# nes_controller_v1_0.net
KiCad netlist of a schematic drawn in EAGLE
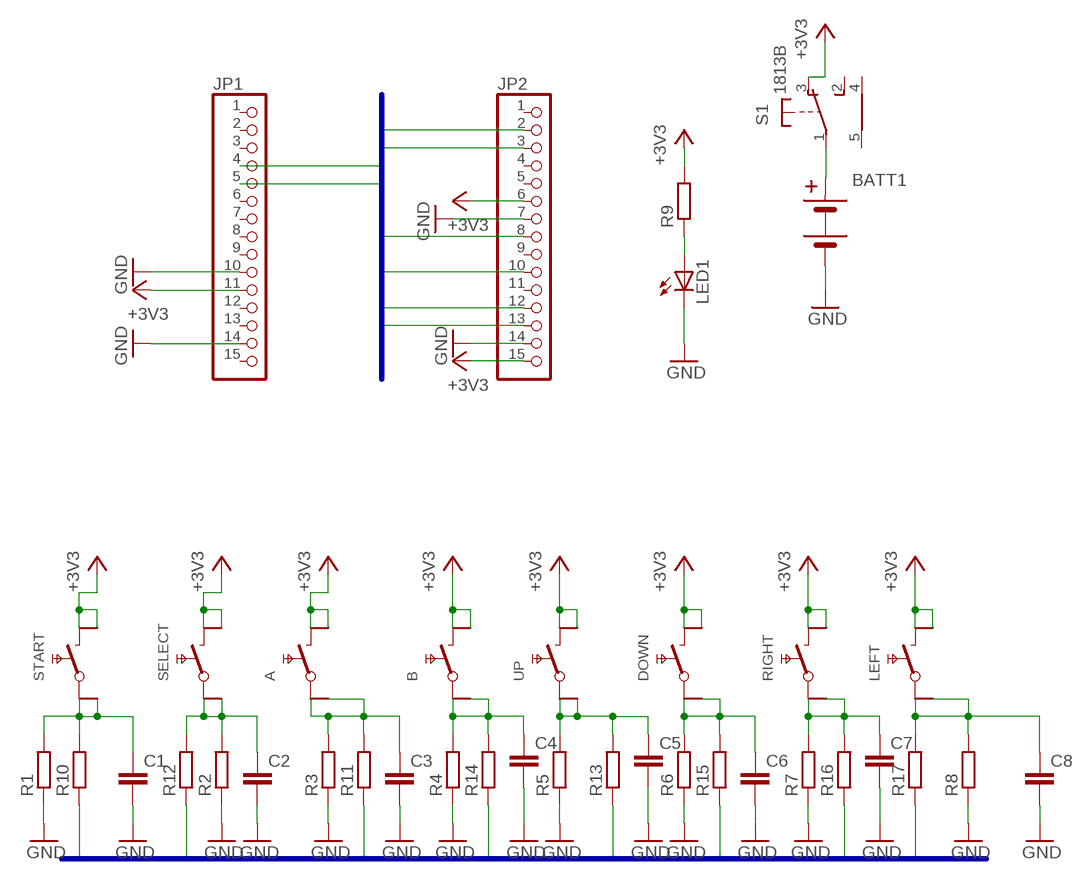
[diagram p0: schematic, sheet 1]

(export (version "E")
  (design (tool "Eeschema 10.0.6"))
  (components
    (comp (ref "A")
      (value "SMDTAST")
      (footprint "eagle-import:SMDTAST")
      (libsource (lib "eagle-import") (part "SMDTAST"))
    )
    (comp (ref "B")
      (value "SMDTAST")
      (footprint "eagle-import:SMDTAST")
      (libsource (lib "eagle-import") (part "SMDTAST"))
    )
    (comp (ref "BATT1")
      (value "BATTERIEHALTER_2X_AAA")
      (footprint "eagle-import:BATTERIEHALTER")
      (libsource (lib "eagle-import") (part "BATTERIEHALTER_2X_AAA"))
    )
    (comp (ref "C1")
      (value "C-EUC0805K")
      (footprint "eagle-import:C0805K")
      (libsource (lib "eagle-import") (part "C-EUC0805K"))
    )
    (comp (ref "C2")
      (value "C-EUC0805K")
      (footprint "eagle-import:C0805K")
      (libsource (lib "eagle-import") (part "C-EUC0805K"))
    )
    (comp (ref "C3")
      (value "C-EUC0805K")
      (footprint "eagle-import:C0805K")
      (libsource (lib "eagle-import") (part "C-EUC0805K"))
    )
    (comp (ref "C4")
      (value "C-EUC0805K")
      (footprint "eagle-import:C0805K")
      (libsource (lib "eagle-import") (part "C-EUC0805K"))
    )
    (comp (ref "C5")
      (value "C-EUC0805K")
      (footprint "eagle-import:C0805K")
      (libsource (lib "eagle-import") (part "C-EUC0805K"))
    )
    (comp (ref "C6")
      (value "C-EUC0805K")
      (footprint "eagle-import:C0805K")
      (libsource (lib "eagle-import") (part "C-EUC0805K"))
    )
    (comp (ref "C7")
      (value "C-EUC0805K")
      (footprint "eagle-import:C0805K")
      (libsource (lib "eagle-import") (part "C-EUC0805K"))
    )
    (comp (ref "C8")
      (value "C-EUC0805K")
      (footprint "eagle-import:C0805K")
      (libsource (lib "eagle-import") (part "C-EUC0805K"))
    )
    (comp (ref "DOWN")
      (value "SMDTAST")
      (footprint "eagle-import:SMDTAST")
      (libsource (lib "eagle-import") (part "SMDTAST"))
    )
    (comp (ref "JP1")
      (value "PINHD-1X15")
      (footprint "eagle-import:1X15")
      (libsource (lib "eagle-import") (part "PINHD-1X15"))
    )
    (comp (ref "JP2")
      (value "PINHD-1X15")
      (footprint "eagle-import:1X15")
      (libsource (lib "eagle-import") (part "PINHD-1X15"))
    )
    (comp (ref "LED1")
      (value "LED3MM")
      (footprint "eagle-import:LED3MM")
      (libsource (lib "eagle-import") (part "LED3MM"))
    )
    (comp (ref "LEFT")
      (value "SMDTAST")
      (footprint "eagle-import:SMDTAST")
      (libsource (lib "eagle-import") (part "SMDTAST"))
    )
    (comp (ref "R1")
      (value "R-EU_R1206")
      (footprint "eagle-import:R1206")
      (libsource (lib "eagle-import") (part "R-EU_R1206"))
    )
    (comp (ref "R2")
      (value "R-EU_R1206")
      (footprint "eagle-import:R1206")
      (libsource (lib "eagle-import") (part "R-EU_R1206"))
    )
    (comp (ref "R3")
      (value "R-EU_R1206")
      (footprint "eagle-import:R1206")
      (libsource (lib "eagle-import") (part "R-EU_R1206"))
    )
    (comp (ref "R4")
      (value "R-EU_R1206")
      (footprint "eagle-import:R1206")
      (libsource (lib "eagle-import") (part "R-EU_R1206"))
    )
    (comp (ref "R5")
      (value "R-EU_R1206")
      (footprint "eagle-import:R1206")
      (libsource (lib "eagle-import") (part "R-EU_R1206"))
    )
    (comp (ref "R6")
      (value "R-EU_R1206")
      (footprint "eagle-import:R1206")
      (libsource (lib "eagle-import") (part "R-EU_R1206"))
    )
    (comp (ref "R7")
      (value "R-EU_R1206")
      (footprint "eagle-import:R1206")
      (libsource (lib "eagle-import") (part "R-EU_R1206"))
    )
    (comp (ref "R8")
      (value "R-EU_R1206")
      (footprint "eagle-import:R1206")
      (libsource (lib "eagle-import") (part "R-EU_R1206"))
    )
    (comp (ref "R9")
      (value "R-EU_R1206")
      (footprint "eagle-import:R1206")
      (libsource (lib "eagle-import") (part "R-EU_R1206"))
    )
    (comp (ref "R10")
      (value "R-EU_R1206")
      (footprint "eagle-import:R1206")
      (libsource (lib "eagle-import") (part "R-EU_R1206"))
    )
    (comp (ref "R11")
      (value "R-EU_R1206")
      (footprint "eagle-import:R1206")
      (libsource (lib "eagle-import") (part "R-EU_R1206"))
    )
    (comp (ref "R12")
      (value "R-EU_R1206")
      (footprint "eagle-import:R1206")
      (libsource (lib "eagle-import") (part "R-EU_R1206"))
    )
    (comp (ref "R13")
      (value "R-EU_R1206")
      (footprint "eagle-import:R1206")
      (libsource (lib "eagle-import") (part "R-EU_R1206"))
    )
    (comp (ref "R14")
      (value "R-EU_R1206")
      (footprint "eagle-import:R1206")
      (libsource (lib "eagle-import") (part "R-EU_R1206"))
    )
    (comp (ref "R15")
      (value "R-EU_R1206")
      (footprint "eagle-import:R1206")
      (libsource (lib "eagle-import") (part "R-EU_R1206"))
    )
    (comp (ref "R16")
      (value "R-EU_R1206")
      (footprint "eagle-import:R1206")
      (libsource (lib "eagle-import") (part "R-EU_R1206"))
    )
    (comp (ref "R17")
      (value "R-EU_R1206")
      (footprint "eagle-import:R1206")
      (libsource (lib "eagle-import") (part "R-EU_R1206"))
    )
    (comp (ref "RIGHT")
      (value "SMDTAST")
      (footprint "eagle-import:SMDTAST")
      (libsource (lib "eagle-import") (part "SMDTAST"))
    )
    (comp (ref "S1")
      (value "1813B")
      (footprint "eagle-import:1813B")
      (libsource (lib "eagle-import") (part "1813B"))
    )
    (comp (ref "SELECT")
      (value "SMDTAST")
      (footprint "eagle-import:SMDTAST")
      (libsource (lib "eagle-import") (part "SMDTAST"))
    )
    (comp (ref "START")
      (value "SMDTAST")
      (footprint "eagle-import:SMDTAST")
      (libsource (lib "eagle-import") (part "SMDTAST"))
    )
    (comp (ref "UP")
      (value "SMDTAST")
      (footprint "eagle-import:SMDTAST")
      (libsource (lib "eagle-import") (part "SMDTAST"))
    )
  )
  (nets
    (net (code "1") (name "+3V3") (class "Default")
      (node (ref "A") (pin "2") (pinfunction "2_2") (pintype "bidirectional"))
      (node (ref "A") (pin "22") (pinfunction "22_22") (pintype "bidirectional"))
      (node (ref "B") (pin "2") (pinfunction "2_2") (pintype "bidirectional"))
      (node (ref "B") (pin "22") (pinfunction "22_22") (pintype "bidirectional"))
      (node (ref "DOWN") (pin "2") (pinfunction "2_2") (pintype "bidirectional"))
      (node (ref "DOWN") (pin "22") (pinfunction "22_22") (pintype "bidirectional"))
      (node (ref "JP1") (pin "11") (pinfunction "11_11") (pintype "passive"))
      (node (ref "JP2") (pin "15") (pinfunction "15_15") (pintype "passive"))
      (node (ref "JP2") (pin "6") (pinfunction "6_6") (pintype "passive"))
      (node (ref "LEFT") (pin "2") (pinfunction "2_2") (pintype "bidirectional"))
      (node (ref "LEFT") (pin "22") (pinfunction "22_22") (pintype "bidirectional"))
      (node (ref "R9") (pin "2") (pinfunction "2_2") (pintype "passive"))
      (node (ref "RIGHT") (pin "2") (pinfunction "2_2") (pintype "bidirectional"))
      (node (ref "RIGHT") (pin "22") (pinfunction "22_22") (pintype "bidirectional"))
      (node (ref "S1") (pin "3") (pinfunction "O_3") (pintype "passive"))
      (node (ref "SELECT") (pin "2") (pinfunction "2_2") (pintype "bidirectional"))
      (node (ref "SELECT") (pin "22") (pinfunction "22_22") (pintype "bidirectional"))
      (node (ref "START") (pin "2") (pinfunction "2_2") (pintype "bidirectional"))
      (node (ref "START") (pin "22") (pinfunction "22_22") (pintype "bidirectional"))
      (node (ref "UP") (pin "2") (pinfunction "2_2") (pintype "bidirectional"))
      (node (ref "UP") (pin "22") (pinfunction "22_22") (pintype "bidirectional"))
    )
    (net (code "2") (name "/A") (class "Default")
      (node (ref "JP1") (pin "5") (pinfunction "5_5") (pintype "passive"))
      (node (ref "R11") (pin "1") (pinfunction "1_1") (pintype "passive"))
    )
    (net (code "3") (name "/B") (class "Default")
      (node (ref "JP1") (pin "4") (pinfunction "4_4") (pintype "passive"))
      (node (ref "R14") (pin "1") (pinfunction "1_1") (pintype "passive"))
    )
    (net (code "4") (name "/DOWN") (class "Default")
      (node (ref "JP2") (pin "10") (pinfunction "10_10") (pintype "passive"))
      (node (ref "R15") (pin "1") (pinfunction "1_1") (pintype "passive"))
    )
    (net (code "5") (name "/LEFT") (class "Default")
      (node (ref "JP2") (pin "3") (pinfunction "3_3") (pintype "passive"))
      (node (ref "R17") (pin "1") (pinfunction "1_1") (pintype "passive"))
    )
    (net (code "6") (name "/RIGHT") (class "Default")
      (node (ref "JP2") (pin "8") (pinfunction "8_8") (pintype "passive"))
      (node (ref "R16") (pin "1") (pinfunction "1_1") (pintype "passive"))
    )
    (net (code "7") (name "/SELECT") (class "Default")
      (node (ref "JP2") (pin "12") (pinfunction "12_12") (pintype "passive"))
      (node (ref "R12") (pin "1") (pinfunction "1_1") (pintype "passive"))
    )
    (net (code "8") (name "/START") (class "Default")
      (node (ref "JP2") (pin "13") (pinfunction "13_13") (pintype "passive"))
      (node (ref "R10") (pin "1") (pinfunction "1_1") (pintype "passive"))
    )
    (net (code "9") (name "/UP") (class "Default")
      (node (ref "JP2") (pin "2") (pinfunction "2_2") (pintype "passive"))
      (node (ref "R13") (pin "1") (pinfunction "1_1") (pintype "passive"))
    )
    (net (code "11") (name "GND") (class "Default")
      (node (ref "BATT1") (pin "P-") (pinfunction "P-_P-") (pintype "bidirectional"))
      (node (ref "C1") (pin "2") (pinfunction "2_2") (pintype "passive"))
      (node (ref "C2") (pin "2") (pinfunction "2_2") (pintype "passive"))
      (node (ref "C3") (pin "2") (pinfunction "2_2") (pintype "passive"))
      (node (ref "C4") (pin "2") (pinfunction "2_2") (pintype "passive"))
      (node (ref "C5") (pin "2") (pinfunction "2_2") (pintype "passive"))
      (node (ref "C6") (pin "2") (pinfunction "2_2") (pintype "passive"))
      (node (ref "C7") (pin "2") (pinfunction "2_2") (pintype "passive"))
      (node (ref "C8") (pin "2") (pinfunction "2_2") (pintype "passive"))
      (node (ref "JP1") (pin "10") (pinfunction "10_10") (pintype "passive"))
      (node (ref "JP1") (pin "14") (pinfunction "14_14") (pintype "passive"))
      (node (ref "JP2") (pin "14") (pinfunction "14_14") (pintype "passive"))
      (node (ref "JP2") (pin "7") (pinfunction "7_7") (pintype "passive"))
      (node (ref "LED1") (pin "K") (pinfunction "C_K") (pintype "passive"))
      (node (ref "R1") (pin "1") (pinfunction "1_1") (pintype "passive"))
      (node (ref "R2") (pin "1") (pinfunction "1_1") (pintype "passive"))
      (node (ref "R3") (pin "1") (pinfunction "1_1") (pintype "passive"))
      (node (ref "R4") (pin "1") (pinfunction "1_1") (pintype "passive"))
      (node (ref "R5") (pin "1") (pinfunction "1_1") (pintype "passive"))
      (node (ref "R6") (pin "1") (pinfunction "1_1") (pintype "passive"))
      (node (ref "R7") (pin "1") (pinfunction "1_1") (pintype "passive"))
      (node (ref "R8") (pin "1") (pinfunction "1_1") (pintype "passive"))
    )
    (net (code "12") (name "Net-(A-Pad1)") (class "Default")
      (node (ref "A") (pin "1") (pinfunction "1_1") (pintype "bidirectional"))
      (node (ref "A") (pin "11") (pinfunction "11_11") (pintype "bidirectional"))
      (node (ref "C3") (pin "1") (pinfunction "1_1") (pintype "passive"))
      (node (ref "R11") (pin "2") (pinfunction "2_2") (pintype "passive"))
      (node (ref "R3") (pin "2") (pinfunction "2_2") (pintype "passive"))
    )
    (net (code "13") (name "Net-(B-Pad1)") (class "Default")
      (node (ref "B") (pin "1") (pinfunction "1_1") (pintype "bidirectional"))
      (node (ref "B") (pin "11") (pinfunction "11_11") (pintype "bidirectional"))
      (node (ref "C4") (pin "1") (pinfunction "1_1") (pintype "passive"))
      (node (ref "R14") (pin "2") (pinfunction "2_2") (pintype "passive"))
      (node (ref "R4") (pin "2") (pinfunction "2_2") (pintype "passive"))
    )
    (net (code "14") (name "Net-(C1-Pad1)") (class "Default")
      (node (ref "C1") (pin "1") (pinfunction "1_1") (pintype "passive"))
      (node (ref "R1") (pin "2") (pinfunction "2_2") (pintype "passive"))
      (node (ref "R10") (pin "2") (pinfunction "2_2") (pintype "passive"))
      (node (ref "START") (pin "1") (pinfunction "1_1") (pintype "bidirectional"))
      (node (ref "START") (pin "11") (pinfunction "11_11") (pintype "bidirectional"))
    )
    (net (code "15") (name "Net-(C2-Pad1)") (class "Default")
      (node (ref "C2") (pin "1") (pinfunction "1_1") (pintype "passive"))
      (node (ref "R12") (pin "2") (pinfunction "2_2") (pintype "passive"))
      (node (ref "R2") (pin "2") (pinfunction "2_2") (pintype "passive"))
      (node (ref "SELECT") (pin "1") (pinfunction "1_1") (pintype "bidirectional"))
      (node (ref "SELECT") (pin "11") (pinfunction "11_11") (pintype "bidirectional"))
    )
    (net (code "16") (name "Net-(C5-Pad1)") (class "Default")
      (node (ref "C5") (pin "1") (pinfunction "1_1") (pintype "passive"))
      (node (ref "R13") (pin "2") (pinfunction "2_2") (pintype "passive"))
      (node (ref "R5") (pin "2") (pinfunction "2_2") (pintype "passive"))
      (node (ref "UP") (pin "1") (pinfunction "1_1") (pintype "bidirectional"))
      (node (ref "UP") (pin "11") (pinfunction "11_11") (pintype "bidirectional"))
    )
    (net (code "17") (name "Net-(C6-Pad1)") (class "Default")
      (node (ref "C6") (pin "1") (pinfunction "1_1") (pintype "passive"))
      (node (ref "DOWN") (pin "1") (pinfunction "1_1") (pintype "bidirectional"))
      (node (ref "DOWN") (pin "11") (pinfunction "11_11") (pintype "bidirectional"))
      (node (ref "R15") (pin "2") (pinfunction "2_2") (pintype "passive"))
      (node (ref "R6") (pin "2") (pinfunction "2_2") (pintype "passive"))
    )
    (net (code "18") (name "Net-(C7-Pad1)") (class "Default")
      (node (ref "C7") (pin "1") (pinfunction "1_1") (pintype "passive"))
      (node (ref "R16") (pin "2") (pinfunction "2_2") (pintype "passive"))
      (node (ref "R7") (pin "2") (pinfunction "2_2") (pintype "passive"))
      (node (ref "RIGHT") (pin "1") (pinfunction "1_1") (pintype "bidirectional"))
      (node (ref "RIGHT") (pin "11") (pinfunction "11_11") (pintype "bidirectional"))
    )
    (net (code "19") (name "Net-(C8-Pad1)") (class "Default")
      (node (ref "C8") (pin "1") (pinfunction "1_1") (pintype "passive"))
      (node (ref "LEFT") (pin "1") (pinfunction "1_1") (pintype "bidirectional"))
      (node (ref "LEFT") (pin "11") (pinfunction "11_11") (pintype "bidirectional"))
      (node (ref "R17") (pin "2") (pinfunction "2_2") (pintype "passive"))
      (node (ref "R8") (pin "2") (pinfunction "2_2") (pintype "passive"))
    )
    (net (code "20") (name "Net-(LED1-PadA)") (class "Default")
      (node (ref "LED1") (pin "A") (pinfunction "A_A") (pintype "passive"))
      (node (ref "R9") (pin "1") (pinfunction "1_1") (pintype "passive"))
    )
    (net (code "21") (name "Net-(S1-W)") (class "Default")
      (node (ref "BATT1") (pin "P+") (pinfunction "P+_P+") (pintype "bidirectional"))
      (node (ref "S1") (pin "1") (pinfunction "W_1") (pintype "passive"))
    )
    (net (code "22") (name "unconnected-(JP1-Pad1)") (class "Default")
      (node (ref "JP1") (pin "1") (pinfunction "1_1") (pintype "passive"))
    )
    (net (code "23") (name "unconnected-(JP1-Pad2)") (class "Default")
      (node (ref "JP1") (pin "2") (pinfunction "2_2") (pintype "passive"))
    )
    (net (code "24") (name "unconnected-(JP1-Pad3)") (class "Default")
      (node (ref "JP1") (pin "3") (pinfunction "3_3") (pintype "passive"))
    )
    (net (code "25") (name "unconnected-(JP1-Pad6)") (class "Default")
      (node (ref "JP1") (pin "6") (pinfunction "6_6") (pintype "passive"))
    )
    (net (code "26") (name "unconnected-(JP1-Pad7)") (class "Default")
      (node (ref "JP1") (pin "7") (pinfunction "7_7") (pintype "passive"))
    )
    (net (code "27") (name "unconnected-(JP1-Pad8)") (class "Default")
      (node (ref "JP1") (pin "8") (pinfunction "8_8") (pintype "passive"))
    )
    (net (code "28") (name "unconnected-(JP1-Pad9)") (class "Default")
      (node (ref "JP1") (pin "9") (pinfunction "9_9") (pintype "passive"))
    )
    (net (code "29") (name "unconnected-(JP1-Pad12)") (class "Default")
      (node (ref "JP1") (pin "12") (pinfunction "12_12") (pintype "passive"))
    )
    (net (code "30") (name "unconnected-(JP1-Pad13)") (class "Default")
      (node (ref "JP1") (pin "13") (pinfunction "13_13") (pintype "passive"))
    )
    (net (code "31") (name "unconnected-(JP1-Pad15)") (class "Default")
      (node (ref "JP1") (pin "15") (pinfunction "15_15") (pintype "passive"))
    )
    (net (code "32") (name "unconnected-(JP2-Pad1)") (class "Default")
      (node (ref "JP2") (pin "1") (pinfunction "1_1") (pintype "passive"))
    )
    (net (code "33") (name "unconnected-(JP2-Pad4)") (class "Default")
      (node (ref "JP2") (pin "4") (pinfunction "4_4") (pintype "passive"))
    )
    (net (code "34") (name "unconnected-(JP2-Pad5)") (class "Default")
      (node (ref "JP2") (pin "5") (pinfunction "5_5") (pintype "passive"))
    )
    (net (code "35") (name "unconnected-(JP2-Pad9)") (class "Default")
      (node (ref "JP2") (pin "9") (pinfunction "9_9") (pintype "passive"))
    )
    (net (code "36") (name "unconnected-(JP2-Pad11)") (class "Default")
      (node (ref "JP2") (pin "11") (pinfunction "11_11") (pintype "passive"))
    )
    (net (code "37") (name "unconnected-(S1-S-Pad2)") (class "Default")
      (node (ref "S1") (pin "2") (pinfunction "S_2") (pintype "passive"))
    )
    (net (code "38") (name "unconnected-(S1-SH1-Pad4)") (class "Default")
      (node (ref "S1") (pin "4") (pinfunction "SH1_4") (pintype "passive"))
    )
    (net (code "39") (name "unconnected-(S1-SH2-Pad5)") (class "Default")
      (node (ref "S1") (pin "5") (pinfunction "SH2_5") (pintype "passive"))
    )
  )
)
